# BOTAO.net
KiCad netlist of a schematic drawn in Altium Designer
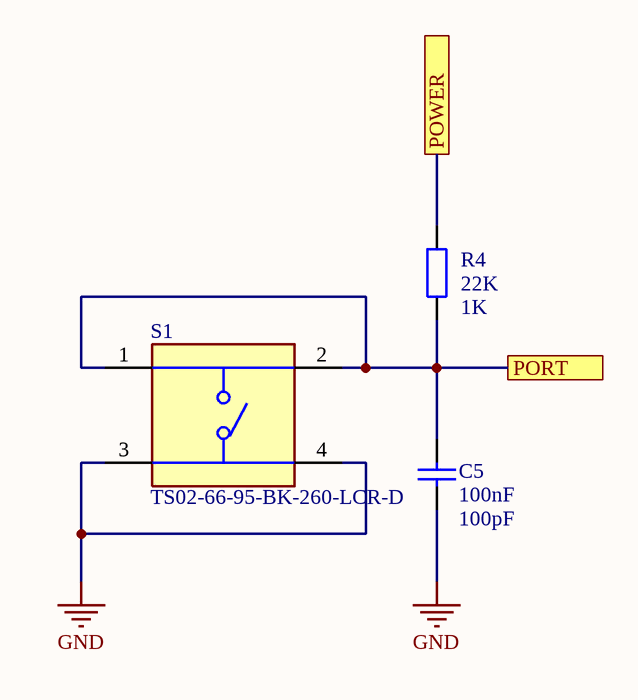
[diagram p0: BOTAO.SchDoc]

(export (version "E")
  (design (tool "Eeschema 10.0.6"))
  (components
    (comp (ref "C5")
      (value "100nF")
      (footprint "RAD-0.3")
      (description "Capacitor")
      (fields (field (name "ALTIUM_VALUE") "100pF") (field (name "PUBLISHER") "Altium Limited"))
      (libsource (lib "Miscellaneous Devices") (part "Cap"))
    )
    (comp (ref "R4")
      (value "22K")
      (footprint "AXIAL-0.4")
      (description "Resistor")
      (fields (field (name "ALTIUM_VALUE") "1K") (field (name "PUBLISHER") "Altium Limited"))
      (libsource (lib "Miscellaneous Devices") (part "Res2"))
    )
    (comp (ref "S1")
      (value "TS02-66-95-BK-260-LCR-D")
      (footprint "SW_TS02-66-95-BK-260-LCR-D")
      (libsource (lib "BOTAO") (part "TS02-66-95-BK-260-LCR-D"))
    )
  )
  (nets
    (net (code "1") (name "/PORT") (class "Default")
      (node (ref "C5") (pin "2") (pinfunction "2_2") (pintype "passive"))
      (node (ref "R4") (pin "1") (pinfunction "1_1") (pintype "passive"))
      (node (ref "S1") (pin "1") (pinfunction "1_1") (pintype "passive"))
      (node (ref "S1") (pin "2") (pinfunction "2_2") (pintype "passive"))
    )
    (net (code "2") (name "/POWER") (class "Default")
      (node (ref "R4") (pin "2") (pinfunction "2_2") (pintype "passive"))
    )
    (net (code "3") (name "GND") (class "Default")
      (node (ref "C5") (pin "1") (pinfunction "1_1") (pintype "passive"))
      (node (ref "S1") (pin "3") (pinfunction "3_3") (pintype "passive"))
      (node (ref "S1") (pin "4") (pinfunction "4_4") (pintype "passive"))
    )
  )
)
